# fluke845_refboard.net
KiCad netlist of a schematic drawn in EAGLE
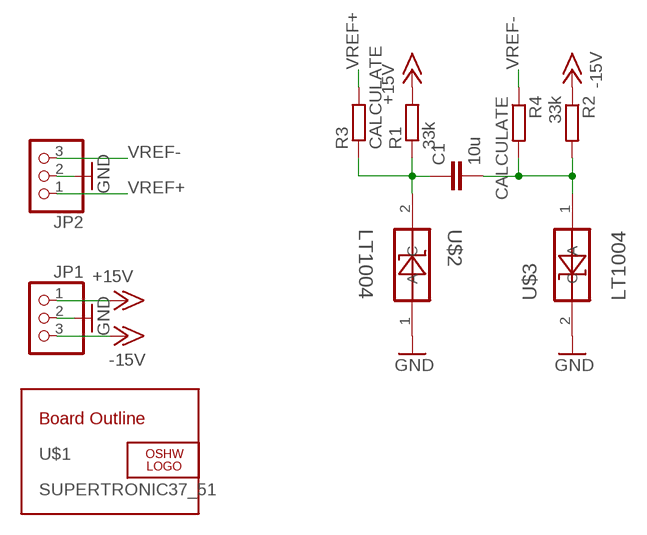
[diagram p0: schematic, sheet 1]

(export (version "E")
  (design (tool "Eeschema 10.0.6"))
  (components
    (comp (ref "C1")
      (value "10u")
      (footprint "eagle-import:C0805")
      (libsource (lib "eagle-import") (part "C-EUC0805"))
    )
    (comp (ref "JP1")
      (value "PINHD-1X3TH_SMALL")
      (footprint "eagle-import:1X03_SMALL")
      (libsource (lib "eagle-import") (part "PINHD-1X3TH_SMALL"))
    )
    (comp (ref "JP2")
      (value "PINHD-1X3TH_SMALL")
      (footprint "eagle-import:1X03_SMALL")
      (libsource (lib "eagle-import") (part "PINHD-1X3TH_SMALL"))
    )
    (comp (ref "LOGO1")
      (value "OSHW_LOGO_8MILX0200-NT")
      (footprint "eagle-import:OSHW_8X200_NOTEXT")
      (libsource (lib "eagle-import") (part "OSHW_LOGO_8MILX0200-NT"))
    )
    (comp (ref "R1")
      (value "33k")
      (footprint "eagle-import:0207_7")
      (libsource (lib "eagle-import") (part "R-EU_0207/7"))
    )
    (comp (ref "R2")
      (value "33k")
      (footprint "eagle-import:0207_7")
      (libsource (lib "eagle-import") (part "R-EU_0207/7"))
    )
    (comp (ref "R3")
      (value "CALCULATE")
      (footprint "eagle-import:0207_7")
      (libsource (lib "eagle-import") (part "R-EU_0207/7"))
    )
    (comp (ref "R4")
      (value "CALCULATE")
      (footprint "eagle-import:0207_7")
      (libsource (lib "eagle-import") (part "R-EU_0207/7"))
    )
    (comp (ref "U$1")
      (value "SUPERTRONIC37_51")
      (footprint "eagle-import:SUPERTRONIC_37_51MM")
      (libsource (lib "eagle-import") (part "SUPERTRONIC37_51"))
    )
    (comp (ref "U$2")
      (value "LT1004")
      (footprint "eagle-import:TO92")
      (libsource (lib "eagle-import") (part "LT1004"))
    )
    (comp (ref "U$3")
      (value "LT1004")
      (footprint "eagle-import:TO92")
      (libsource (lib "eagle-import") (part "LT1004"))
    )
  )
  (nets
    (net (code "1") (name "+15V") (class "Default")
      (node (ref "JP1") (pin "1") (pinfunction "1_1") (pintype "passive"))
      (node (ref "R1") (pin "2") (pinfunction "2_2") (pintype "passive"))
    )
    (net (code "2") (name "-15V") (class "Default")
      (node (ref "JP1") (pin "3") (pinfunction "3_3") (pintype "passive"))
      (node (ref "R2") (pin "1") (pinfunction "1_1") (pintype "passive"))
    )
    (net (code "3") (name "/VREF+") (class "Default")
      (node (ref "JP2") (pin "1") (pinfunction "1_1") (pintype "passive"))
      (node (ref "R3") (pin "2") (pinfunction "2_2") (pintype "passive"))
    )
    (net (code "4") (name "/VREF-") (class "Default")
      (node (ref "JP2") (pin "3") (pinfunction "3_3") (pintype "passive"))
      (node (ref "R4") (pin "1") (pinfunction "1_1") (pintype "passive"))
    )
    (net (code "5") (name "GND") (class "Default")
      (node (ref "JP1") (pin "2") (pinfunction "2_2") (pintype "passive"))
      (node (ref "JP2") (pin "2") (pinfunction "2_2") (pintype "passive"))
      (node (ref "U$2") (pin "1") (pinfunction "A_1") (pintype "input"))
      (node (ref "U$3") (pin "2") (pinfunction "C_2") (pintype "input"))
    )
    (net (code "6") (name "Net-(U$2-C)") (class "Default")
      (node (ref "C1") (pin "1") (pinfunction "1_1") (pintype "passive"))
      (node (ref "R1") (pin "1") (pinfunction "1_1") (pintype "passive"))
      (node (ref "R3") (pin "1") (pinfunction "1_1") (pintype "passive"))
      (node (ref "U$2") (pin "2") (pinfunction "C_2") (pintype "input"))
    )
    (net (code "7") (name "Net-(U$3-A)") (class "Default")
      (node (ref "C1") (pin "2") (pinfunction "2_2") (pintype "passive"))
      (node (ref "R2") (pin "2") (pinfunction "2_2") (pintype "passive"))
      (node (ref "R4") (pin "2") (pinfunction "2_2") (pintype "passive"))
      (node (ref "U$3") (pin "1") (pinfunction "A_1") (pintype "input"))
    )
  )
)
